# ProDoc_Board1_2025-08-02.net
KiCad netlist of a schematic drawn in EasyEDA Pro
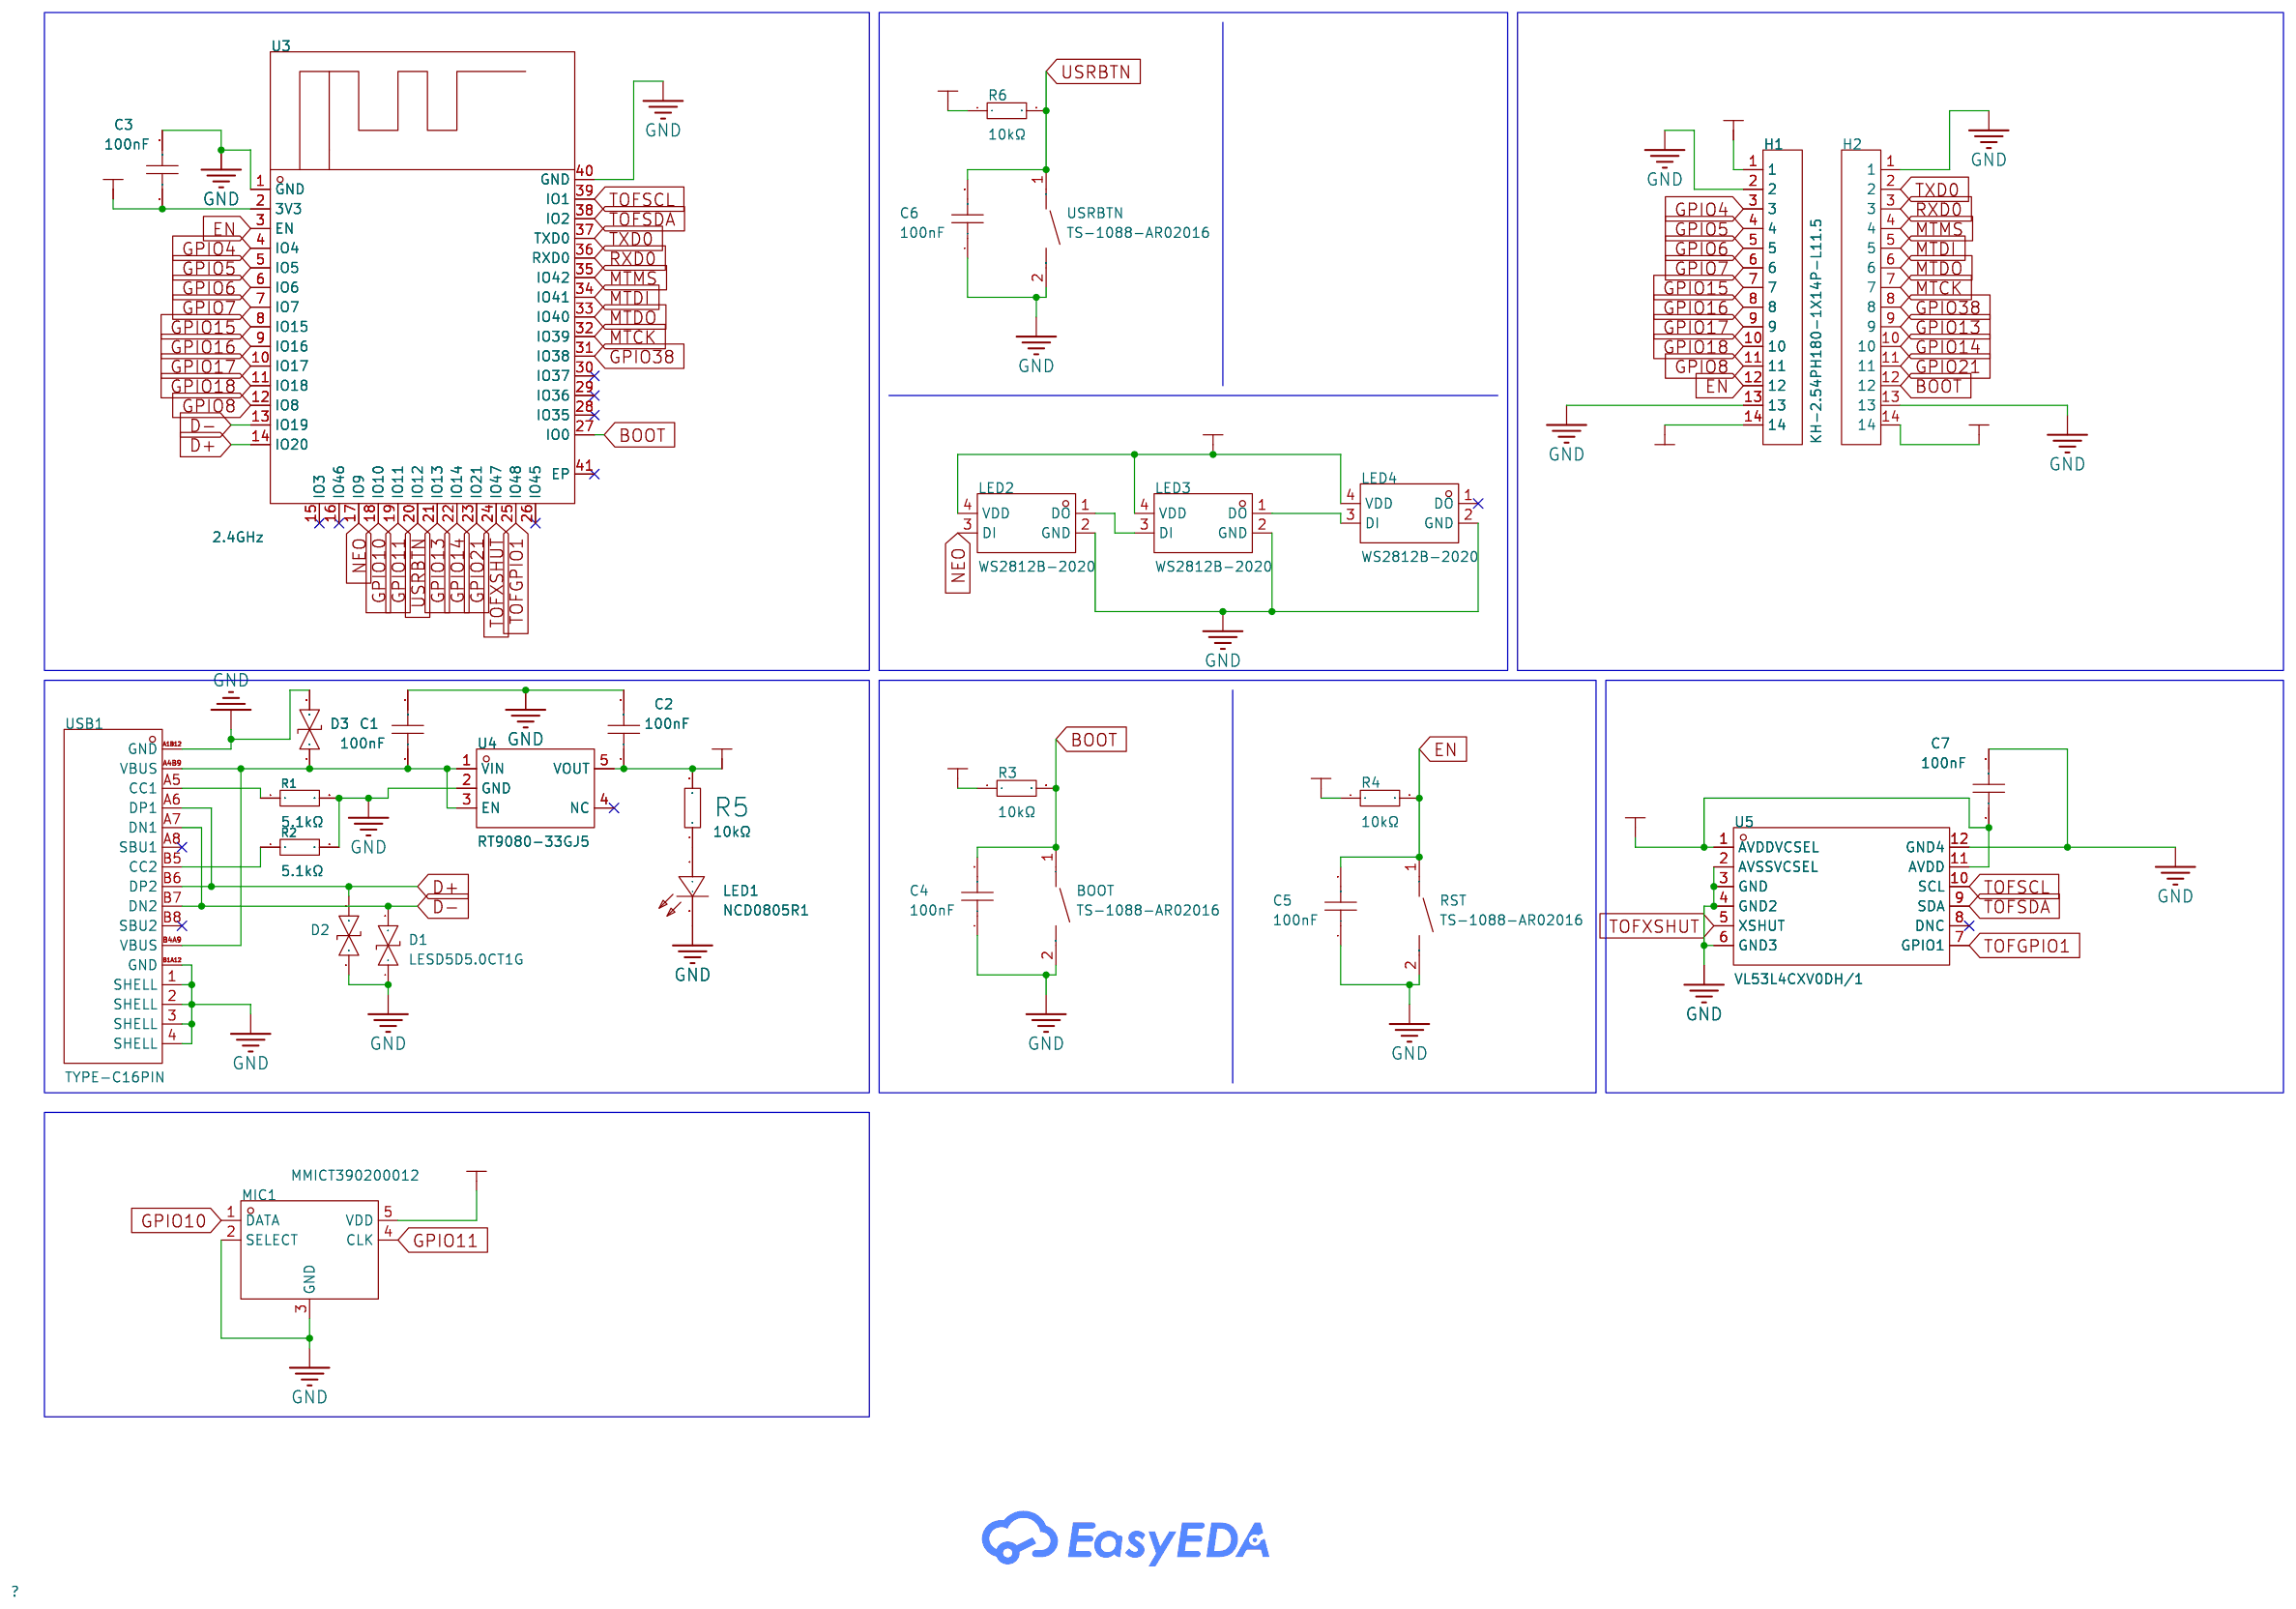
[diagram p0: schematic sheet]

(export (version "E")
  (design (tool "Eeschema 10.0.6"))
  (components
    (comp (ref "BOOT")
      (value "TS-1088-AR02016")
      (footprint "easyedapro:SW-SMD_L3.9-W3.0-P4.45")
      (fields (field (name "Manufacturer") "XUNPU(讯普)"))
      (libsource (lib "easyedapro") (part "TS-1088-AR02016"))
    )
    (comp (ref "C1")
      (value "100nF")
      (footprint "easyedapro:C0805")
      (description "Capacitance:100nF Tolerance:±10% Tolerance:±10% Voltage Rating:50V Temperature Coefficient:X7R")
      (fields (field (name "Manufacturer Part") "C0805B104K500NT") (field (name "Manufacturer") "TORCH(火炬)"))
      (libsource (lib "easyedapro") (part "C0805B104K500NT"))
    )
    (comp (ref "C2")
      (value "100nF")
      (footprint "easyedapro:C0805")
      (description "Capacitance:100nF Tolerance:±10% Tolerance:±10% Voltage Rating:50V Temperature Coefficient:X7R")
      (fields (field (name "Manufacturer Part") "C0805B104K500NT") (field (name "Manufacturer") "TORCH(火炬)"))
      (libsource (lib "easyedapro") (part "C0805B104K500NT"))
    )
    (comp (ref "C3")
      (value "100nF")
      (footprint "easyedapro:C0805")
      (description "Capacitance:100nF Tolerance:±10% Tolerance:±10% Voltage Rating:50V Temperature Coefficient:X7R")
      (fields (field (name "Manufacturer Part") "C0805B104K500NT") (field (name "Manufacturer") "TORCH(火炬)"))
      (libsource (lib "easyedapro") (part "C0805B104K500NT"))
    )
    (comp (ref "C4")
      (value "100nF")
      (footprint "easyedapro:C0805")
      (description "Capacitance:100nF Tolerance:±10% Tolerance:±10% Voltage Rating:50V Temperature Coefficient:X7R")
      (fields (field (name "Manufacturer Part") "C0805B104K500NT") (field (name "Manufacturer") "TORCH(火炬)"))
      (libsource (lib "easyedapro") (part "C0805B104K500NT"))
    )
    (comp (ref "C5")
      (value "100nF")
      (footprint "easyedapro:C0805")
      (description "Capacitance:100nF Tolerance:±10% Tolerance:±10% Voltage Rating:50V Temperature Coefficient:X7R")
      (fields (field (name "Manufacturer Part") "C0805B104K500NT") (field (name "Manufacturer") "TORCH(火炬)"))
      (libsource (lib "easyedapro") (part "C0805B104K500NT"))
    )
    (comp (ref "C6")
      (value "100nF")
      (footprint "easyedapro:C0805")
      (description "Capacitance:100nF Tolerance:±10% Tolerance:±10% Voltage Rating:50V Temperature Coefficient:X7R")
      (fields (field (name "Manufacturer Part") "C0805B104K500NT") (field (name "Manufacturer") "TORCH(火炬)"))
      (libsource (lib "easyedapro") (part "C0805B104K500NT"))
    )
    (comp (ref "C7")
      (value "100nF")
      (footprint "easyedapro:C0805")
      (description "Capacitance:100nF Tolerance:±10% Tolerance:±10% Voltage Rating:50V Temperature Coefficient:X7R")
      (fields (field (name "Manufacturer Part") "C0805B104K500NT") (field (name "Manufacturer") "TORCH(火炬)"))
      (libsource (lib "easyedapro") (part "C0805B104K500NT"))
    )
    (comp (ref "D1")
      (value "LESD5D5.0CT1G")
      (footprint "easyedapro:SOD-523_L1.2-W0.8-LS1.6-BI")
      (fields (field (name "Manufacturer") "LRC(乐山无线电)"))
      (libsource (lib "easyedapro") (part "LESD5D5.0CT1G"))
    )
    (comp (ref "D2")
      (value "LESD5D5.0CT1G")
      (footprint "easyedapro:SOD-523_L1.2-W0.8-LS1.6-BI")
      (fields (field (name "Manufacturer") "LRC(乐山无线电)"))
      (libsource (lib "easyedapro") (part "LESD5D5.0CT1G"))
    )
    (comp (ref "D3")
      (value "LESD5D5.0CT1G")
      (footprint "easyedapro:SOD-523_L1.2-W0.8-LS1.6-BI")
      (fields (field (name "Manufacturer") "LRC(乐山无线电)"))
      (libsource (lib "easyedapro") (part "LESD5D5.0CT1G"))
    )
    (comp (ref "H1")
      (value "KH-2.54PH180-1X14P-L11.5")
      (footprint "easyedapro:HDR-TH_14P-P2.54-V-M")
      (fields (field (name "Manufacturer") "kinghelm(金航标)"))
      (libsource (lib "easyedapro") (part "KH-2.54PH180-1X14P-L11.5"))
    )
    (comp (ref "H2")
      (value "KH-2.54PH180-1X14P-L11.5")
      (footprint "easyedapro:HDR-TH_14P-P2.54-V-M")
      (fields (field (name "Manufacturer") "kinghelm(金航标)"))
      (libsource (lib "easyedapro") (part "KH-2.54PH180-1X14P-L11.5"))
    )
    (comp (ref "LED1")
      (value "NCD0805R1")
      (footprint "easyedapro:LED0805-R-RD")
      (fields (field (name "Manufacturer") "国星光电"))
      (libsource (lib "easyedapro") (part "FC-2012HRK-620D"))
    )
    (comp (ref "LED2")
      (value "WS2812B-2020")
      (footprint "easyedapro:LED-SMD_4P-L2.0-W2.0-TL_WS2812B-2020")
      (fields (field (name "Manufacturer") "worldsemi"))
      (libsource (lib "easyedapro") (part "WS2812B-2020"))
    )
    (comp (ref "LED3")
      (value "WS2812B-2020")
      (footprint "easyedapro:LED-SMD_4P-L2.0-W2.0-TL_WS2812B-2020")
      (fields (field (name "Manufacturer") "worldsemi"))
      (libsource (lib "easyedapro") (part "WS2812B-2020"))
    )
    (comp (ref "LED4")
      (value "WS2812B-2020")
      (footprint "easyedapro:LED-SMD_4P-L2.0-W2.0-TL_WS2812B-2020")
      (fields (field (name "Manufacturer") "worldsemi"))
      (libsource (lib "easyedapro") (part "WS2812B-2020"))
    )
    (comp (ref "MIC1")
      (value "MMICT390200012")
      (footprint "easyedapro:MIC-SMD_5P-L3.5-W2.7-TL_MMICT390200012")
      (fields (field (name "Manufacturer") "TDK InvenSense(应美盛)"))
      (libsource (lib "easyedapro") (part "MMICT390200012"))
    )
    (comp (ref "R1")
      (value "5.1kΩ")
      (footprint "easyedapro:R0805")
      (description "Resistance:5.1kΩ Tolerance:±1% Tolerance:±1% Power(Watts):0.125W")
      (fields (field (name "Manufacturer Part") "RMC08055.1K1%N") (field (name "Manufacturer") "Tyohm(幸亚电阻)"))
      (libsource (lib "easyedapro") (part "RMC08055.1K1%N"))
    )
    (comp (ref "R2")
      (value "5.1kΩ")
      (footprint "easyedapro:R0805")
      (description "Resistance:5.1kΩ Tolerance:±1% Tolerance:±1% Power(Watts):0.125W")
      (fields (field (name "Manufacturer Part") "RMC08055.1K1%N") (field (name "Manufacturer") "Tyohm(幸亚电阻)"))
      (libsource (lib "easyedapro") (part "RMC08055.1K1%N"))
    )
    (comp (ref "R3")
      (value "10kΩ")
      (fields (field (name "Manufacturer Part") "PTFR0805B10K0N9") (field (name "Manufacturer") "RESI(开步睿思)"))
      (libsource (lib "easyedapro") (part "0805W8F0000T5E"))
    )
    (comp (ref "R4")
      (value "10kΩ")
      (fields (field (name "Manufacturer Part") "PTFR0805B10K0N9") (field (name "Manufacturer") "RESI(开步睿思)"))
      (libsource (lib "easyedapro") (part "0805W8F0000T5E"))
    )
    (comp (ref "R5")
      (value "10kΩ")
      (footprint "easyedapro:R0603")
      (fields
        (field (name "Manufacturer Part") "0603WAF1002T5E")
        (field (name "Manufacturer") "UNI-ROYAL(厚声)")
      )
      (libsource (lib "easyedapro") (part "0603WAF1002T5E"))
    )
    (comp (ref "R6")
      (value "10kΩ")
      (fields (field (name "Manufacturer Part") "PTFR0805B10K0N9") (field (name "Manufacturer") "RESI(开步睿思)"))
      (libsource (lib "easyedapro") (part "0805W8F0000T5E"))
    )
    (comp (ref "RST")
      (value "TS-1088-AR02016")
      (footprint "easyedapro:SW-SMD_L3.9-W3.0-P4.45")
      (fields (field (name "Manufacturer") "XUNPU(讯普)"))
      (libsource (lib "easyedapro") (part "TS-1088-AR02016"))
    )
    (comp (ref "U3")
      (value "2.4GHz")
      (footprint "easyedapro:WIFIM-SMD_ESP32-S3-WROOM-1-N8")
      (description "Core Processor:ESP32-S3 Chip Support Interface:I2C；GPIO；SPI；PWM；ADC；UART；USB；I2S Frequency:2.4GHz")
      (fields
        (field (name "Manufacturer Part") "ESP32-S3-WROOM-1-N8")
        (field (name "Manufacturer") "ESPRESSIF(乐鑫)")
      )
      (libsource (lib "easyedapro") (part "ESP32-S3-WROOM-1-N8"))
    )
    (comp (ref "U4")
      (value "RT9080-33GJ5")
      (footprint "easyedapro:TSOT-23-5_L2.9-W1.6-P0.95-LS2.8-BL")
      (fields (field (name "Manufacturer") "RICHTEK(立锜)"))
      (libsource (lib "easyedapro") (part "RT9080-33GJ5"))
    )
    (comp (ref "U5")
      (value "VL53L4CXV0DH/1")
      (footprint "easyedapro:OPTO-SMD_VL53L1CXV0FY-1")
      (fields (field (name "Manufacturer") "ST(意法半导体)"))
      (libsource (lib "easyedapro") (part "VL53L4CXV0DH/1"))
    )
    (comp (ref "USB1")
      (value "TYPE-C16PIN")
      (footprint "easyedapro:USB-C-SMD_TYPE-C16PIN")
      (fields (field (name "Manufacturer") "SHOU HAN(首韩)"))
      (libsource (lib "easyedapro") (part "TYPE-C16PIN"))
    )
    (comp (ref "USRBTN")
      (value "TS-1088-AR02016")
      (footprint "easyedapro:SW-SMD_L3.9-W3.0-P4.45")
      (fields (field (name "Manufacturer") "XUNPU(讯普)"))
      (libsource (lib "easyedapro") (part "TS-1088-AR02016"))
    )
  )
  (nets
    (net (code "1") (name "+3.3V") (class "Default")
      (node (ref "C2") (pin "1") (pinfunction "1_1") (pintype "unspecified"))
      (node (ref "C3") (pin "1") (pinfunction "1_1") (pintype "unspecified"))
      (node (ref "C7") (pin "1") (pinfunction "1_1") (pintype "unspecified"))
      (node (ref "H1") (pin "1") (pinfunction "1_1") (pintype "unspecified"))
      (node (ref "H1") (pin "14") (pinfunction "14_14") (pintype "unspecified"))
      (node (ref "H2") (pin "14") (pinfunction "14_14") (pintype "unspecified"))
      (node (ref "LED2") (pin "4") (pinfunction "VDD_4") (pintype "unspecified"))
      (node (ref "LED3") (pin "4") (pinfunction "VDD_4") (pintype "unspecified"))
      (node (ref "LED4") (pin "4") (pinfunction "VDD_4") (pintype "unspecified"))
      (node (ref "MIC1") (pin "5") (pinfunction "VDD_5") (pintype "unspecified"))
      (node (ref "R3") (pin "1") (pinfunction "1_1") (pintype "input"))
      (node (ref "R4") (pin "1") (pinfunction "1_1") (pintype "input"))
      (node (ref "R5") (pin "2") (pinfunction "2_2") (pintype "input"))
      (node (ref "R6") (pin "1") (pinfunction "1_1") (pintype "input"))
      (node (ref "U3") (pin "2") (pinfunction "3V3_2") (pintype "unspecified"))
      (node (ref "U4") (pin "5") (pinfunction "VOUT_5") (pintype "unspecified"))
      (node (ref "U5") (pin "1") (pinfunction "AVDDVCSEL_1") (pintype "unspecified"))
      (node (ref "U5") (pin "11") (pinfunction "AVDD_11") (pintype "unspecified"))
    )
    (net (code "2") (name "BOOT") (class "Default")
      (node (ref "BOOT") (pin "1") (pinfunction "1_1") (pintype "unspecified"))
      (node (ref "C4") (pin "2") (pinfunction "2_2") (pintype "unspecified"))
      (node (ref "H2") (pin "12") (pinfunction "12_12") (pintype "unspecified"))
      (node (ref "R3") (pin "2") (pinfunction "2_2") (pintype "input"))
      (node (ref "U3") (pin "27") (pinfunction "IO0_27") (pintype "unspecified"))
    )
    (net (code "3") (name "D+") (class "Default")
      (node (ref "D2") (pin "2") (pinfunction "2_2") (pintype "unspecified"))
      (node (ref "U3") (pin "14") (pinfunction "IO20_14") (pintype "unspecified"))
      (node (ref "USB1") (pin "A6") (pinfunction "DP1_A6") (pintype "unspecified"))
      (node (ref "USB1") (pin "B6") (pinfunction "DP2_B6") (pintype "unspecified"))
    )
    (net (code "4") (name "D-") (class "Default")
      (node (ref "D1") (pin "2") (pinfunction "2_2") (pintype "unspecified"))
      (node (ref "U3") (pin "13") (pinfunction "IO19_13") (pintype "unspecified"))
      (node (ref "USB1") (pin "A7") (pinfunction "DN1_A7") (pintype "unspecified"))
      (node (ref "USB1") (pin "B7") (pinfunction "DN2_B7") (pintype "unspecified"))
    )
    (net (code "5") (name "EN") (class "Default")
      (node (ref "C5") (pin "2") (pinfunction "2_2") (pintype "unspecified"))
      (node (ref "H1") (pin "12") (pinfunction "12_12") (pintype "unspecified"))
      (node (ref "R4") (pin "2") (pinfunction "2_2") (pintype "input"))
      (node (ref "RST") (pin "1") (pinfunction "1_1") (pintype "unspecified"))
      (node (ref "U3") (pin "3") (pinfunction "EN_3") (pintype "unspecified"))
    )
    (net (code "6") (name "GND") (class "Default")
      (node (ref "BOOT") (pin "2") (pinfunction "2_2") (pintype "unspecified"))
      (node (ref "C1") (pin "2") (pinfunction "2_2") (pintype "unspecified"))
      (node (ref "C2") (pin "2") (pinfunction "2_2") (pintype "unspecified"))
      (node (ref "C3") (pin "2") (pinfunction "2_2") (pintype "unspecified"))
      (node (ref "C4") (pin "1") (pinfunction "1_1") (pintype "unspecified"))
      (node (ref "C5") (pin "1") (pinfunction "1_1") (pintype "unspecified"))
      (node (ref "C6") (pin "1") (pinfunction "1_1") (pintype "unspecified"))
      (node (ref "C7") (pin "2") (pinfunction "2_2") (pintype "unspecified"))
      (node (ref "D1") (pin "1") (pinfunction "1_1") (pintype "unspecified"))
      (node (ref "D2") (pin "1") (pinfunction "1_1") (pintype "unspecified"))
      (node (ref "D3") (pin "2") (pinfunction "2_2") (pintype "unspecified"))
      (node (ref "H1") (pin "13") (pinfunction "13_13") (pintype "unspecified"))
      (node (ref "H1") (pin "2") (pinfunction "2_2") (pintype "unspecified"))
      (node (ref "H2") (pin "1") (pinfunction "1_1") (pintype "unspecified"))
      (node (ref "H2") (pin "13") (pinfunction "13_13") (pintype "unspecified"))
      (node (ref "LED1") (pin "2") (pinfunction "-_2") (pintype "unspecified"))
      (node (ref "LED2") (pin "2") (pinfunction "GND_2") (pintype "unspecified"))
      (node (ref "LED3") (pin "2") (pinfunction "GND_2") (pintype "unspecified"))
      (node (ref "LED4") (pin "2") (pinfunction "GND_2") (pintype "unspecified"))
      (node (ref "MIC1") (pin "2") (pinfunction "SELECT_2") (pintype "unspecified"))
      (node (ref "MIC1") (pin "3") (pinfunction "GND_3") (pintype "unspecified"))
      (node (ref "R1") (pin "2") (pinfunction "2_2") (pintype "input"))
      (node (ref "R2") (pin "2") (pinfunction "2_2") (pintype "input"))
      (node (ref "RST") (pin "2") (pinfunction "2_2") (pintype "unspecified"))
      (node (ref "U3") (pin "1") (pinfunction "GND_1") (pintype "unspecified"))
      (node (ref "U3") (pin "40") (pinfunction "GND_40") (pintype "unspecified"))
      (node (ref "U4") (pin "2") (pinfunction "GND_2") (pintype "unspecified"))
      (node (ref "U5") (pin "12") (pinfunction "GND4_12") (pintype "unspecified"))
      (node (ref "U5") (pin "2") (pinfunction "AVSSVCSEL_2") (pintype "unspecified"))
      (node (ref "U5") (pin "3") (pinfunction "GND_3") (pintype "unspecified"))
      (node (ref "U5") (pin "4") (pinfunction "GND2_4") (pintype "unspecified"))
      (node (ref "U5") (pin "6") (pinfunction "GND3_6") (pintype "unspecified"))
      (node (ref "USB1") (pin "1") (pinfunction "SHELL_1") (pintype "unspecified"))
      (node (ref "USB1") (pin "2") (pinfunction "SHELL_2") (pintype "unspecified"))
      (node (ref "USB1") (pin "3") (pinfunction "SHELL_3") (pintype "unspecified"))
      (node (ref "USB1") (pin "4") (pinfunction "SHELL_4") (pintype "unspecified"))
      (node (ref "USB1") (pin "A1B12") (pinfunction "GND_A1B12") (pintype "unspecified"))
      (node (ref "USB1") (pin "B1A12") (pinfunction "GND_B1A12") (pintype "unspecified"))
      (node (ref "USRBTN") (pin "2") (pinfunction "2_2") (pintype "unspecified"))
    )
    (net (code "7") (name "GPIO4") (class "Default")
      (node (ref "H1") (pin "3") (pinfunction "3_3") (pintype "unspecified"))
      (node (ref "U3") (pin "4") (pinfunction "IO4_4") (pintype "unspecified"))
    )
    (net (code "8") (name "GPIO5") (class "Default")
      (node (ref "H1") (pin "4") (pinfunction "4_4") (pintype "unspecified"))
      (node (ref "U3") (pin "5") (pinfunction "IO5_5") (pintype "unspecified"))
    )
    (net (code "9") (name "GPIO6") (class "Default")
      (node (ref "H1") (pin "5") (pinfunction "5_5") (pintype "unspecified"))
      (node (ref "U3") (pin "6") (pinfunction "IO6_6") (pintype "unspecified"))
    )
    (net (code "10") (name "GPIO7") (class "Default")
      (node (ref "H1") (pin "6") (pinfunction "6_6") (pintype "unspecified"))
      (node (ref "U3") (pin "7") (pinfunction "IO7_7") (pintype "unspecified"))
    )
    (net (code "11") (name "GPIO8") (class "Default")
      (node (ref "H1") (pin "11") (pinfunction "11_11") (pintype "unspecified"))
      (node (ref "U3") (pin "12") (pinfunction "IO8_12") (pintype "unspecified"))
    )
    (net (code "12") (name "GPIO10") (class "Default")
      (node (ref "MIC1") (pin "1") (pinfunction "DATA_1") (pintype "unspecified"))
      (node (ref "U3") (pin "18") (pinfunction "IO10_18") (pintype "unspecified"))
    )
    (net (code "13") (name "GPIO11") (class "Default")
      (node (ref "MIC1") (pin "4") (pinfunction "CLK_4") (pintype "unspecified"))
      (node (ref "U3") (pin "19") (pinfunction "IO11_19") (pintype "unspecified"))
    )
    (net (code "14") (name "GPIO13") (class "Default")
      (node (ref "H2") (pin "9") (pinfunction "9_9") (pintype "unspecified"))
      (node (ref "U3") (pin "21") (pinfunction "IO13_21") (pintype "unspecified"))
    )
    (net (code "15") (name "GPIO14") (class "Default")
      (node (ref "H2") (pin "10") (pinfunction "10_10") (pintype "unspecified"))
      (node (ref "U3") (pin "22") (pinfunction "IO14_22") (pintype "unspecified"))
    )
    (net (code "16") (name "GPIO15") (class "Default")
      (node (ref "H1") (pin "7") (pinfunction "7_7") (pintype "unspecified"))
      (node (ref "U3") (pin "8") (pinfunction "IO15_8") (pintype "unspecified"))
    )
    (net (code "17") (name "GPIO16") (class "Default")
      (node (ref "H1") (pin "8") (pinfunction "8_8") (pintype "unspecified"))
      (node (ref "U3") (pin "9") (pinfunction "IO16_9") (pintype "unspecified"))
    )
    (net (code "18") (name "GPIO17") (class "Default")
      (node (ref "H1") (pin "9") (pinfunction "9_9") (pintype "unspecified"))
      (node (ref "U3") (pin "10") (pinfunction "IO17_10") (pintype "unspecified"))
    )
    (net (code "19") (name "GPIO18") (class "Default")
      (node (ref "H1") (pin "10") (pinfunction "10_10") (pintype "unspecified"))
      (node (ref "U3") (pin "11") (pinfunction "IO18_11") (pintype "unspecified"))
    )
    (net (code "20") (name "GPIO21") (class "Default")
      (node (ref "H2") (pin "11") (pinfunction "11_11") (pintype "unspecified"))
      (node (ref "U3") (pin "23") (pinfunction "IO21_23") (pintype "unspecified"))
    )
    (net (code "21") (name "GPIO38") (class "Default")
      (node (ref "H2") (pin "8") (pinfunction "8_8") (pintype "unspecified"))
      (node (ref "U3") (pin "31") (pinfunction "IO38_31") (pintype "unspecified"))
    )
    (net (code "22") (name "MTCK") (class "Default")
      (node (ref "H2") (pin "7") (pinfunction "7_7") (pintype "unspecified"))
      (node (ref "U3") (pin "32") (pinfunction "IO39_32") (pintype "unspecified"))
    )
    (net (code "23") (name "MTDI") (class "Default")
      (node (ref "H2") (pin "5") (pinfunction "5_5") (pintype "unspecified"))
      (node (ref "U3") (pin "34") (pinfunction "IO41_34") (pintype "unspecified"))
    )
    (net (code "24") (name "MTDO") (class "Default")
      (node (ref "H2") (pin "6") (pinfunction "6_6") (pintype "unspecified"))
      (node (ref "U3") (pin "33") (pinfunction "IO40_33") (pintype "unspecified"))
    )
    (net (code "25") (name "MTMS") (class "Default")
      (node (ref "H2") (pin "4") (pinfunction "4_4") (pintype "unspecified"))
      (node (ref "U3") (pin "35") (pinfunction "IO42_35") (pintype "unspecified"))
    )
    (net (code "26") (name "NEO") (class "Default")
      (node (ref "LED2") (pin "3") (pinfunction "DI_3") (pintype "unspecified"))
      (node (ref "U3") (pin "17") (pinfunction "IO9_17") (pintype "unspecified"))
    )
    (net (code "27") (name "Net-(LED1-+)") (class "Default")
      (node (ref "LED1") (pin "1") (pinfunction "+_1") (pintype "unspecified"))
      (node (ref "R5") (pin "1") (pinfunction "1_1") (pintype "input"))
    )
    (net (code "28") (name "Net-(LED2-DO)") (class "Default")
      (node (ref "LED2") (pin "1") (pinfunction "DO_1") (pintype "unspecified"))
      (node (ref "LED3") (pin "3") (pinfunction "DI_3") (pintype "unspecified"))
    )
    (net (code "29") (name "Net-(LED3-DO)") (class "Default")
      (node (ref "LED3") (pin "1") (pinfunction "DO_1") (pintype "unspecified"))
      (node (ref "LED4") (pin "3") (pinfunction "DI_3") (pintype "unspecified"))
    )
    (net (code "30") (name "Net-(U4-EN)") (class "Default")
      (node (ref "C1") (pin "1") (pinfunction "1_1") (pintype "unspecified"))
      (node (ref "D3") (pin "1") (pinfunction "1_1") (pintype "unspecified"))
      (node (ref "U4") (pin "1") (pinfunction "VIN_1") (pintype "unspecified"))
      (node (ref "U4") (pin "3") (pinfunction "EN_3") (pintype "unspecified"))
      (node (ref "USB1") (pin "A4B9") (pinfunction "VBUS_A4B9") (pintype "unspecified"))
      (node (ref "USB1") (pin "B4A9") (pinfunction "VBUS_B4A9") (pintype "unspecified"))
    )
    (net (code "31") (name "Net-(USB1-CC1)") (class "Default")
      (node (ref "R1") (pin "1") (pinfunction "1_1") (pintype "input"))
      (node (ref "USB1") (pin "A5") (pinfunction "CC1_A5") (pintype "unspecified"))
    )
    (net (code "32") (name "Net-(USB1-CC2)") (class "Default")
      (node (ref "R2") (pin "1") (pinfunction "1_1") (pintype "input"))
      (node (ref "USB1") (pin "B5") (pinfunction "CC2_B5") (pintype "unspecified"))
    )
    (net (code "33") (name "RXD0") (class "Default")
      (node (ref "H2") (pin "3") (pinfunction "3_3") (pintype "unspecified"))
      (node (ref "U3") (pin "36") (pinfunction "RXD0_36") (pintype "unspecified"))
    )
    (net (code "34") (name "TOFGPIO1") (class "Default")
      (node (ref "U3") (pin "25") (pinfunction "IO48_25") (pintype "unspecified"))
      (node (ref "U5") (pin "7") (pinfunction "GPIO1_7") (pintype "unspecified"))
    )
    (net (code "35") (name "TOFSCL") (class "Default")
      (node (ref "U3") (pin "39") (pinfunction "IO1_39") (pintype "unspecified"))
      (node (ref "U5") (pin "10") (pinfunction "SCL_10") (pintype "unspecified"))
    )
    (net (code "36") (name "TOFSDA") (class "Default")
      (node (ref "U3") (pin "38") (pinfunction "IO2_38") (pintype "unspecified"))
      (node (ref "U5") (pin "9") (pinfunction "SDA_9") (pintype "unspecified"))
    )
    (net (code "37") (name "TOFXSHUT") (class "Default")
      (node (ref "U3") (pin "24") (pinfunction "IO47_24") (pintype "unspecified"))
      (node (ref "U5") (pin "5") (pinfunction "XSHUT_5") (pintype "unspecified"))
    )
    (net (code "38") (name "TXD0") (class "Default")
      (node (ref "H2") (pin "2") (pinfunction "2_2") (pintype "unspecified"))
      (node (ref "U3") (pin "37") (pinfunction "TXD0_37") (pintype "unspecified"))
    )
    (net (code "39") (name "USRBTN") (class "Default")
      (node (ref "C6") (pin "2") (pinfunction "2_2") (pintype "unspecified"))
      (node (ref "R6") (pin "2") (pinfunction "2_2") (pintype "input"))
      (node (ref "U3") (pin "20") (pinfunction "IO12_20") (pintype "unspecified"))
      (node (ref "USRBTN") (pin "1") (pinfunction "1_1") (pintype "unspecified"))
    )
    (net (code "40") (name "unconnected-(LED4-DO-Pad1)") (class "Default")
      (node (ref "LED4") (pin "1") (pinfunction "DO_1") (pintype "unspecified+no_connect"))
    )
    (net (code "41") (name "unconnected-(U3-EP-Pad41)") (class "Default")
      (node (ref "U3") (pin "41") (pinfunction "EP_41") (pintype "unspecified+no_connect"))
    )
    (net (code "42") (name "unconnected-(U3-IO3-Pad15)") (class "Default")
      (node (ref "U3") (pin "15") (pinfunction "IO3_15") (pintype "unspecified+no_connect"))
    )
    (net (code "43") (name "unconnected-(U3-IO35-Pad28)") (class "Default")
      (node (ref "U3") (pin "28") (pinfunction "IO35_28") (pintype "unspecified+no_connect"))
    )
    (net (code "44") (name "unconnected-(U3-IO36-Pad29)") (class "Default")
      (node (ref "U3") (pin "29") (pinfunction "IO36_29") (pintype "unspecified+no_connect"))
    )
    (net (code "45") (name "unconnected-(U3-IO37-Pad30)") (class "Default")
      (node (ref "U3") (pin "30") (pinfunction "IO37_30") (pintype "unspecified+no_connect"))
    )
    (net (code "46") (name "unconnected-(U3-IO45-Pad26)") (class "Default")
      (node (ref "U3") (pin "26") (pinfunction "IO45_26") (pintype "unspecified+no_connect"))
    )
    (net (code "47") (name "unconnected-(U3-IO46-Pad16)") (class "Default")
      (node (ref "U3") (pin "16") (pinfunction "IO46_16") (pintype "unspecified+no_connect"))
    )
    (net (code "48") (name "unconnected-(U4-NC-Pad4)") (class "Default")
      (node (ref "U4") (pin "4") (pinfunction "NC_4") (pintype "unspecified+no_connect"))
    )
    (net (code "49") (name "unconnected-(U5-DNC-Pad8)") (class "Default")
      (node (ref "U5") (pin "8") (pinfunction "DNC_8") (pintype "unspecified+no_connect"))
    )
    (net (code "50") (name "unconnected-(USB1-SBU1-PadA8)") (class "Default")
      (node (ref "USB1") (pin "A8") (pinfunction "SBU1_A8") (pintype "unspecified+no_connect"))
    )
    (net (code "51") (name "unconnected-(USB1-SBU2-PadB8)") (class "Default")
      (node (ref "USB1") (pin "B8") (pinfunction "SBU2_B8") (pintype "unspecified+no_connect"))
    )
  )
)
